# MB1280_Fanout.net
KiCad netlist of a schematic drawn in Altium Designer
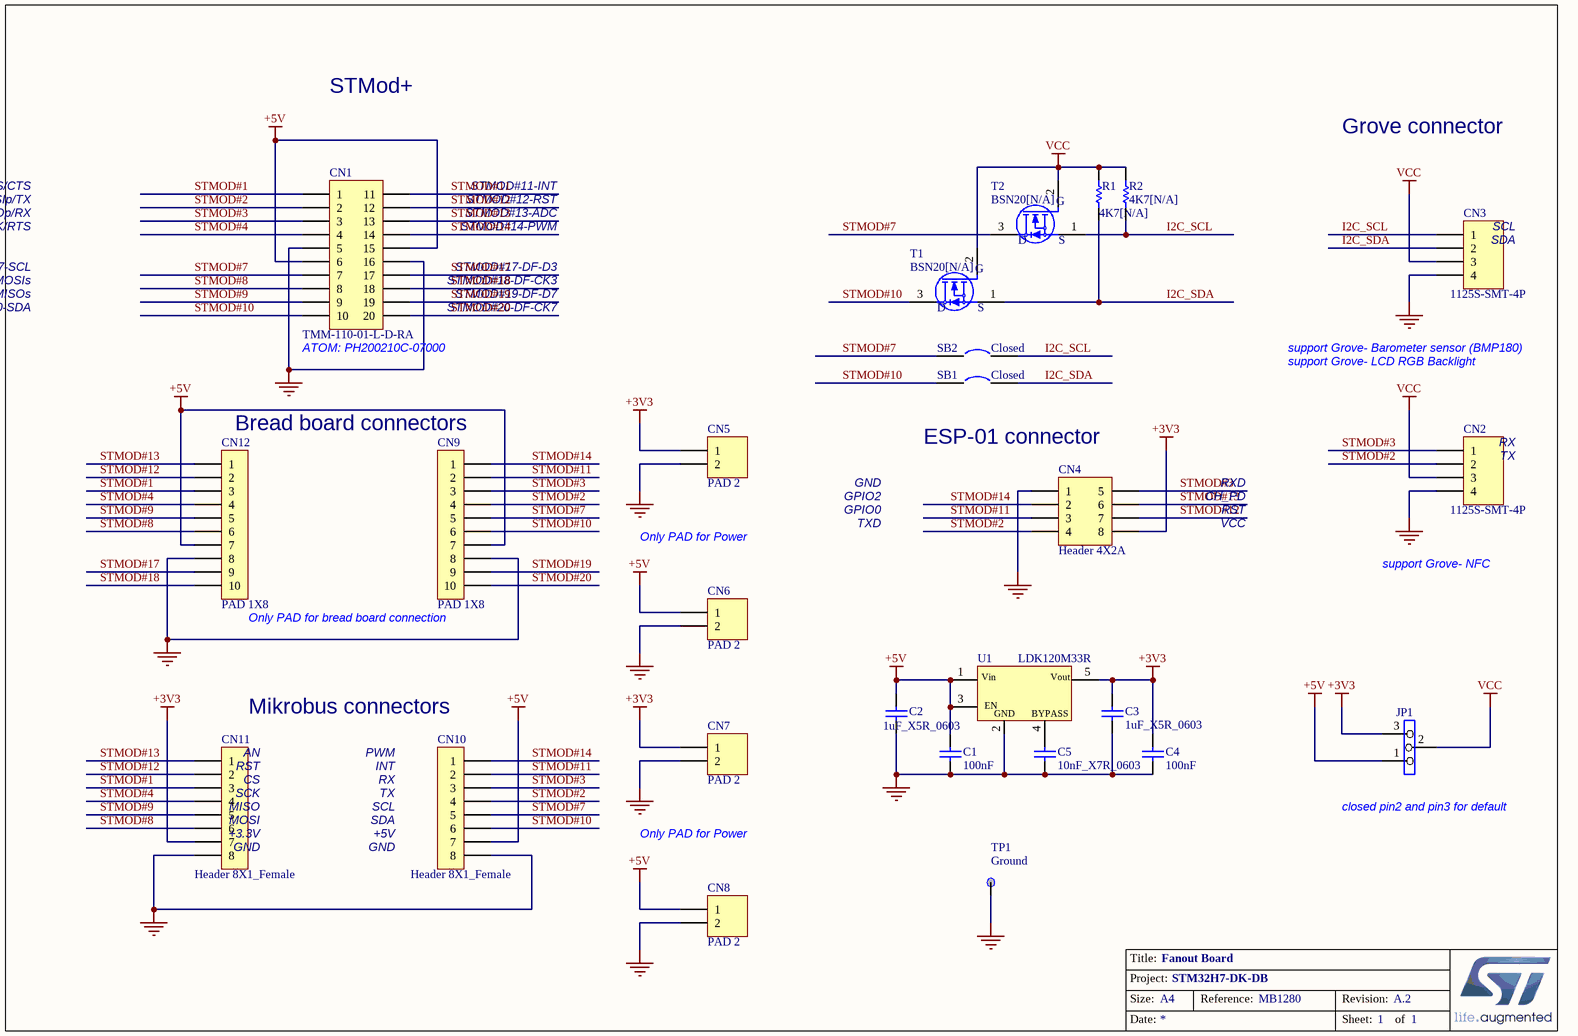
[diagram p0: MB1280_Fanout.SchDoc]

(export (version "E")
  (design (tool "Eeschema 10.0.6"))
  (components
    (comp (ref "C1")
      (value "100nF")
      (footprint "0603C")
      (description "Capacitor 0402 / 0603 / 0805")
      (libsource (lib "MCD_TOOLS") (part "Capacitor_ST"))
    )
    (comp (ref "C2")
      (value "1uF_X5R_0603")
      (footprint "0603C")
      (description "0603  X5R 1礔")
      (fields (field (name "TOLERANCE") "10%"))
      (libsource (lib "MB963_1") (part "CAP SMD 0603  X5R 1礔 25V 10%"))
    )
    (comp (ref "C3")
      (value "1uF_X5R_0603")
      (footprint "0603C")
      (description "0603  X5R 1礔")
      (fields (field (name "TOLERANCE") "10%"))
      (libsource (lib "MB963_1") (part "CAP SMD 0603  X5R 1礔 25V 10%"))
    )
    (comp (ref "C4")
      (value "100nF")
      (footprint "0603C")
      (description "Capacitor 0402 / 0603 / 0805")
      (libsource (lib "MCD_TOOLS") (part "Capacitor_ST"))
    )
    (comp (ref "C5")
      (value "10nF_X7R_0603")
      (footprint "0603C")
      (description "0603  X7R 10NF")
      (fields (field (name "TOLERANCE") "10%"))
      (libsource (lib "MB963_1") (part "CAP SMD 0603  X7R 10000PF 50V 10%"))
    )
    (comp (ref "CN1")
      (value "TMM-110-01-L-D-RA")
      (footprint "2*10_MALE_2MM_H")
      (description "Header, 10-Pin, Dual row")
      (fields (field (name "PUBLISHER") "Altium Limited"))
      (libsource (lib "Miscellaneous Connectors") (part "Header 10X2A"))
    )
    (comp (ref "CN2")
      (value "1125S-SMT-4P")
      (footprint "1X4_MALE_C")
      (fields (field (name "PUBLISHER") "Altium Limited"))
      (libsource (lib "Miscellaneous Connectors") (part "Header 4"))
    )
    (comp (ref "CN3")
      (value "1125S-SMT-4P")
      (footprint "1X4_MALE_C")
      (fields (field (name "PUBLISHER") "Altium Limited"))
      (libsource (lib "Miscellaneous Connectors") (part "Header 4"))
    )
    (comp (ref "CN4")
      (value "Header 4X2A")
      (footprint "HDR2X4_CEN1")
      (description "Header, 4-Pin, Dual row")
      (fields (field (name "PUBLISHER") "Altium Limited"))
      (libsource (lib "Miscellaneous Connectors") (part "Header 4X2A"))
    )
    (comp (ref "CN5")
      (value "PAD 2")
      (footprint "HDR_2X1_2R54")
      (description "Header, 2-Pin")
      (fields (field (name "PUBLISHER") "Altium Limited"))
      (libsource (lib "Miscellaneous Connectors") (part "Header 2"))
    )
    (comp (ref "CN6")
      (value "PAD 2")
      (footprint "HDR_2X1_2R54")
      (description "Header, 2-Pin")
      (fields (field (name "PUBLISHER") "Altium Limited"))
      (libsource (lib "Miscellaneous Connectors") (part "Header 2"))
    )
    (comp (ref "CN7")
      (value "PAD 2")
      (footprint "HDR_2X1_2R54")
      (description "Header, 2-Pin")
      (fields (field (name "PUBLISHER") "Altium Limited"))
      (libsource (lib "Miscellaneous Connectors") (part "Header 2"))
    )
    (comp (ref "CN8")
      (value "PAD 2")
      (footprint "HDR_2X1_2R54")
      (description "Header, 2-Pin")
      (fields (field (name "PUBLISHER") "Altium Limited"))
      (libsource (lib "Miscellaneous Connectors") (part "Header 2"))
    )
    (comp (ref "CN9")
      (value "PAD 1X8")
      (footprint "1*10P_FEMALE")
      (description "Header, 10-Pin, Single row,female")
      (fields (field (name "PUBLISHER") "Altium Limited"))
      (libsource (lib "Nucleo_64") (part "Header 10X1_Female"))
    )
    (comp (ref "CN10")
      (value "Header 8X1_Female")
      (footprint "1*8P_FEMALE")
      (description "Header, 8-Pin, Single row,female")
      (fields (field (name "PUBLISHER") "Altium Limited"))
      (libsource (lib "") (part "Header 8X1_Female_1"))
    )
    (comp (ref "CN11")
      (value "Header 8X1_Female")
      (footprint "1*8P_FEMALE")
      (description "Header, 8-Pin, Single row,female")
      (fields (field (name "PUBLISHER") "Altium Limited"))
      (libsource (lib "Nucleo_64") (part "Header 8X1_Female"))
    )
    (comp (ref "CN12")
      (value "PAD 1X8")
      (footprint "1*10P_FEMALE")
      (description "Header, 10-Pin, Single row,female")
      (fields (field (name "PUBLISHER") "Altium Limited"))
      (libsource (lib "") (part "Header 10X1_Female_1"))
    )
    (comp (ref "JP1") (value "~") (footprint "SIP3") (libsource (lib "STR910_SCHLIB") (part "Jumper3")))
    (comp (ref "R1")
      (value "4K7[N/A]")
      (footprint "0603R")
      (description "Resistor")
      (fields (field (name "PUBLISHER") "Altium Limited"))
      (libsource (lib "Miscellaneous Devices") (part "res1"))
    )
    (comp (ref "R2")
      (value "4K7[N/A]")
      (footprint "0603R")
      (description "Resistor")
      (fields (field (name "PUBLISHER") "Altium Limited"))
      (libsource (lib "Miscellaneous Devices") (part "res1"))
    )
    (comp (ref "SB1")
      (value "Closed")
      (footprint "SB_0603")
      (description "Circuit Breaker")
      (fields (field (name "PUBLISHER") "Altium Limited"))
      (libsource (lib "Miscellaneous Devices") (part "Circuit Breaker"))
    )
    (comp (ref "SB2")
      (value "Closed")
      (footprint "SB_0603")
      (description "Circuit Breaker")
      (fields (field (name "PUBLISHER") "Altium Limited"))
      (libsource (lib "Miscellaneous Devices") (part "Circuit Breaker"))
    )
    (comp (ref "T1") (value "BSN20[N/A]") (footprint "SOT23-213") (libsource (lib "MB525") (part "2N7000")))
    (comp (ref "T2") (value "BSN20[N/A]") (footprint "SOT23-213") (libsource (lib "MB525") (part "2N7000")))
    (comp (ref "TP1") (value "Ground") (footprint "TP_C4MM_PAD") (libsource (lib "*") (part "TP")))
    (comp (ref "U1")
      (value "LDK120M33R")
      (footprint "SOT-23-5L")
      (description "200 mA low quiescent current very low noise LDO")
      (libsource (lib "MB1246") (part "LDK120M33R"))
    )
  )
  (nets
    (net (code "1") (name "+3V3") (class "Default")
      (node (ref "C3") (pin "1") (pinfunction "1_1") (pintype "passive"))
      (node (ref "C4") (pin "2") (pinfunction "2_2") (pintype "passive"))
      (node (ref "CN11") (pin "7") (pinfunction "7_7") (pintype "passive"))
      (node (ref "CN4") (pin "8") (pinfunction "8_8") (pintype "passive"))
      (node (ref "CN5") (pin "1") (pinfunction "1_1") (pintype "passive"))
      (node (ref "CN7") (pin "1") (pinfunction "1_1") (pintype "passive"))
      (node (ref "JP1") (pin "3") (pintype "passive"))
      (node (ref "U1") (pin "5") (pinfunction "Vout_5") (pintype "passive"))
    )
    (net (code "2") (name "+5V") (class "Default")
      (node (ref "C1") (pin "2") (pinfunction "2_2") (pintype "passive"))
      (node (ref "C2") (pin "2") (pinfunction "2_2") (pintype "passive"))
      (node (ref "CN1") (pin "15") (pinfunction "15_15") (pintype "passive"))
      (node (ref "CN1") (pin "6") (pinfunction "6_6") (pintype "passive"))
      (node (ref "CN10") (pin "7") (pinfunction "7_7") (pintype "passive"))
      (node (ref "CN12") (pin "7") (pinfunction "7_7") (pintype "passive"))
      (node (ref "CN6") (pin "1") (pinfunction "1_1") (pintype "passive"))
      (node (ref "CN8") (pin "1") (pinfunction "1_1") (pintype "passive"))
      (node (ref "CN9") (pin "7") (pinfunction "7_7") (pintype "passive"))
      (node (ref "JP1") (pin "1") (pintype "passive"))
      (node (ref "U1") (pin "1") (pinfunction "Vin_1") (pintype "passive"))
      (node (ref "U1") (pin "3") (pinfunction "CE_3") (pintype "passive"))
    )
    (net (code "3") (name "/I2C_SCL") (class "Default")
      (node (ref "CN3") (pin "1") (pinfunction "1_1") (pintype "passive"))
      (node (ref "R2") (pin "1") (pinfunction "1_1") (pintype "passive"))
      (node (ref "SB2") (pin "2") (pinfunction "2_2") (pintype "passive"))
      (node (ref "T2") (pin "1") (pinfunction "S_1") (pintype "passive"))
    )
    (net (code "4") (name "/I2C_SDA") (class "Default")
      (node (ref "CN3") (pin "2") (pinfunction "2_2") (pintype "passive"))
      (node (ref "R1") (pin "1") (pinfunction "1_1") (pintype "passive"))
      (node (ref "SB1") (pin "2") (pinfunction "2_2") (pintype "passive"))
      (node (ref "T1") (pin "1") (pinfunction "S_1") (pintype "passive"))
    )
    (net (code "5") (name "/STMOD#1") (class "Default")
      (node (ref "CN1") (pin "1") (pinfunction "1_1") (pintype "passive"))
      (node (ref "CN11") (pin "3") (pinfunction "3_3") (pintype "passive"))
      (node (ref "CN12") (pin "3") (pinfunction "3_3") (pintype "passive"))
    )
    (net (code "6") (name "/STMOD#2") (class "Default")
      (node (ref "CN1") (pin "2") (pinfunction "2_2") (pintype "passive"))
      (node (ref "CN10") (pin "4") (pinfunction "4_4") (pintype "passive"))
      (node (ref "CN2") (pin "2") (pinfunction "2_2") (pintype "passive"))
      (node (ref "CN4") (pin "4") (pinfunction "4_4") (pintype "passive"))
      (node (ref "CN9") (pin "4") (pinfunction "4_4") (pintype "passive"))
    )
    (net (code "7") (name "/STMOD#3") (class "Default")
      (node (ref "CN1") (pin "3") (pinfunction "3_3") (pintype "passive"))
      (node (ref "CN10") (pin "3") (pinfunction "3_3") (pintype "passive"))
      (node (ref "CN2") (pin "1") (pinfunction "1_1") (pintype "passive"))
      (node (ref "CN4") (pin "5") (pinfunction "5_5") (pintype "passive"))
      (node (ref "CN9") (pin "3") (pinfunction "3_3") (pintype "passive"))
    )
    (net (code "8") (name "/STMOD#4") (class "Default")
      (node (ref "CN1") (pin "4") (pinfunction "4_4") (pintype "passive"))
      (node (ref "CN11") (pin "4") (pinfunction "4_4") (pintype "passive"))
      (node (ref "CN12") (pin "4") (pinfunction "4_4") (pintype "passive"))
    )
    (net (code "9") (name "/STMOD#7") (class "Default")
      (node (ref "CN1") (pin "7") (pinfunction "7_7") (pintype "passive"))
      (node (ref "CN10") (pin "5") (pinfunction "5_5") (pintype "passive"))
      (node (ref "CN9") (pin "5") (pinfunction "5_5") (pintype "passive"))
      (node (ref "SB2") (pin "1") (pinfunction "1_1") (pintype "passive"))
      (node (ref "T2") (pin "3") (pinfunction "D_3") (pintype "passive"))
    )
    (net (code "10") (name "/STMOD#8") (class "Default")
      (node (ref "CN1") (pin "8") (pinfunction "8_8") (pintype "passive"))
      (node (ref "CN11") (pin "6") (pinfunction "6_6") (pintype "passive"))
      (node (ref "CN12") (pin "6") (pinfunction "6_6") (pintype "passive"))
    )
    (net (code "11") (name "/STMOD#9") (class "Default")
      (node (ref "CN1") (pin "9") (pinfunction "9_9") (pintype "passive"))
      (node (ref "CN11") (pin "5") (pinfunction "5_5") (pintype "passive"))
      (node (ref "CN12") (pin "5") (pinfunction "5_5") (pintype "passive"))
    )
    (net (code "12") (name "/STMOD#10") (class "Default")
      (node (ref "CN1") (pin "10") (pinfunction "10_10") (pintype "passive"))
      (node (ref "CN10") (pin "6") (pinfunction "6_6") (pintype "passive"))
      (node (ref "CN9") (pin "6") (pinfunction "6_6") (pintype "passive"))
      (node (ref "SB1") (pin "1") (pinfunction "1_1") (pintype "passive"))
      (node (ref "T1") (pin "3") (pinfunction "D_3") (pintype "passive"))
    )
    (net (code "13") (name "/STMOD#11") (class "Default")
      (node (ref "CN1") (pin "11") (pinfunction "11_11") (pintype "passive"))
      (node (ref "CN10") (pin "2") (pinfunction "2_2") (pintype "passive"))
      (node (ref "CN4") (pin "3") (pinfunction "3_3") (pintype "passive"))
      (node (ref "CN9") (pin "2") (pinfunction "2_2") (pintype "passive"))
    )
    (net (code "14") (name "/STMOD#12") (class "Default")
      (node (ref "CN1") (pin "12") (pinfunction "12_12") (pintype "passive"))
      (node (ref "CN11") (pin "2") (pinfunction "2_2") (pintype "passive"))
      (node (ref "CN12") (pin "2") (pinfunction "2_2") (pintype "passive"))
      (node (ref "CN4") (pin "7") (pinfunction "7_7") (pintype "passive"))
    )
    (net (code "15") (name "/STMOD#13") (class "Default")
      (node (ref "CN1") (pin "13") (pinfunction "13_13") (pintype "passive"))
      (node (ref "CN11") (pin "1") (pinfunction "1_1") (pintype "passive"))
      (node (ref "CN12") (pin "1") (pinfunction "1_1") (pintype "passive"))
      (node (ref "CN4") (pin "6") (pinfunction "6_6") (pintype "passive"))
    )
    (net (code "16") (name "/STMOD#14") (class "Default")
      (node (ref "CN1") (pin "14") (pinfunction "14_14") (pintype "passive"))
      (node (ref "CN10") (pin "1") (pinfunction "1_1") (pintype "passive"))
      (node (ref "CN4") (pin "2") (pinfunction "2_2") (pintype "passive"))
      (node (ref "CN9") (pin "1") (pinfunction "1_1") (pintype "passive"))
    )
    (net (code "17") (name "/STMOD#17") (class "Default")
      (node (ref "CN1") (pin "17") (pinfunction "17_17") (pintype "passive"))
      (node (ref "CN12") (pin "9") (pinfunction "9_9") (pintype "passive"))
    )
    (net (code "18") (name "/STMOD#18") (class "Default")
      (node (ref "CN1") (pin "18") (pinfunction "18_18") (pintype "passive"))
      (node (ref "CN12") (pin "10") (pinfunction "10_10") (pintype "passive"))
    )
    (net (code "19") (name "/STMOD#19") (class "Default")
      (node (ref "CN1") (pin "19") (pinfunction "19_19") (pintype "passive"))
      (node (ref "CN9") (pin "9") (pinfunction "9_9") (pintype "passive"))
    )
    (net (code "20") (name "/STMOD#20") (class "Default")
      (node (ref "CN1") (pin "20") (pinfunction "20_20") (pintype "passive"))
      (node (ref "CN9") (pin "10") (pinfunction "10_10") (pintype "passive"))
    )
    (net (code "21") (name "GND") (class "Default")
      (node (ref "C1") (pin "1") (pinfunction "1_1") (pintype "passive"))
      (node (ref "C2") (pin "1") (pinfunction "1_1") (pintype "passive"))
      (node (ref "C3") (pin "2") (pinfunction "2_2") (pintype "passive"))
      (node (ref "C4") (pin "1") (pinfunction "1_1") (pintype "passive"))
      (node (ref "C5") (pin "1") (pinfunction "1_1") (pintype "passive"))
      (node (ref "CN1") (pin "16") (pinfunction "16_16") (pintype "passive"))
      (node (ref "CN1") (pin "5") (pinfunction "5_5") (pintype "passive"))
      (node (ref "CN10") (pin "8") (pinfunction "8_8") (pintype "passive"))
      (node (ref "CN11") (pin "8") (pinfunction "8_8") (pintype "passive"))
      (node (ref "CN12") (pin "8") (pinfunction "8_8") (pintype "passive"))
      (node (ref "CN2") (pin "4") (pinfunction "4_4") (pintype "passive"))
      (node (ref "CN3") (pin "4") (pinfunction "4_4") (pintype "passive"))
      (node (ref "CN4") (pin "1") (pinfunction "1_1") (pintype "passive"))
      (node (ref "CN5") (pin "2") (pinfunction "2_2") (pintype "passive"))
      (node (ref "CN6") (pin "2") (pinfunction "2_2") (pintype "passive"))
      (node (ref "CN7") (pin "2") (pinfunction "2_2") (pintype "passive"))
      (node (ref "CN8") (pin "2") (pinfunction "2_2") (pintype "passive"))
      (node (ref "CN9") (pin "8") (pinfunction "8_8") (pintype "passive"))
      (node (ref "TP1") (pin "1") (pinfunction "1_1") (pintype "passive"))
      (node (ref "U1") (pin "2") (pinfunction "GND_2") (pintype "passive"))
    )
    (net (code "22") (name "Net-(U1-BYPASS)") (class "Default")
      (node (ref "C5") (pin "2") (pinfunction "2_2") (pintype "passive"))
      (node (ref "U1") (pin "4") (pinfunction "BYPASS_4") (pintype "passive"))
    )
    (net (code "23") (name "VCC") (class "Default")
      (node (ref "CN2") (pin "3") (pinfunction "3_3") (pintype "passive"))
      (node (ref "CN3") (pin "3") (pinfunction "3_3") (pintype "passive"))
      (node (ref "JP1") (pin "2") (pintype "passive"))
      (node (ref "R1") (pin "2") (pinfunction "2_2") (pintype "passive"))
      (node (ref "R2") (pin "2") (pinfunction "2_2") (pintype "passive"))
      (node (ref "T1") (pin "2") (pinfunction "G_2") (pintype "passive"))
      (node (ref "T2") (pin "2") (pinfunction "G_2") (pintype "passive"))
    )
  )
)
